# 20190105_ORIGAMI_V1-1-V.net
KiCad netlist of a schematic drawn in EAGLE
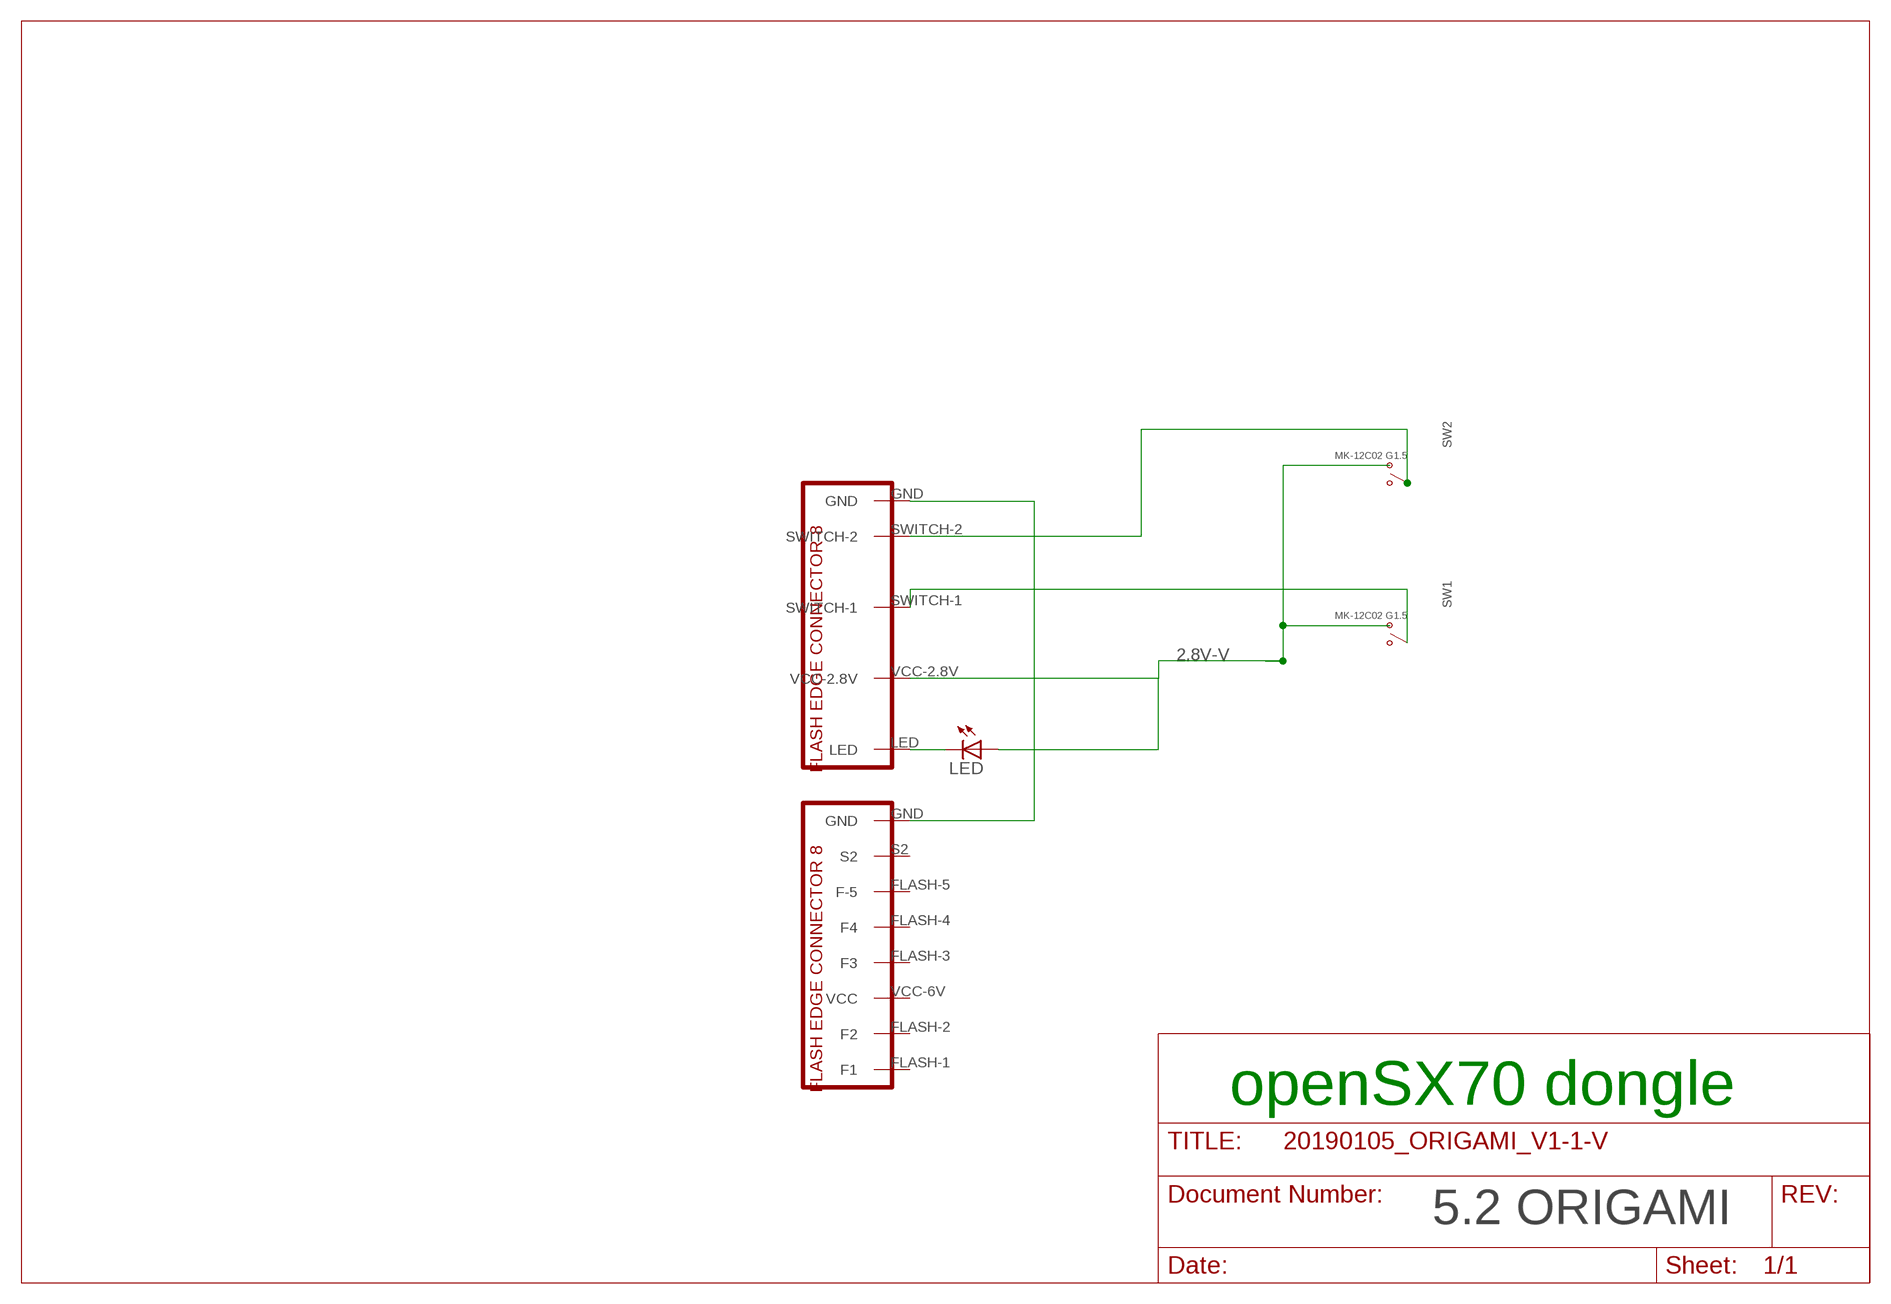
[diagram p0: schematic, sheet 1]

(export (version "E")
  (design (tool "Eeschema 10.0.6"))
  (components
    (comp (ref "LED")
      (value "LEDCHIP-LED0805")
      (footprint "eagle-import:CHIP-LED0805")
      (libsource (lib "eagle-import") (part "LEDCHIP-LED0805"))
    )
    (comp (ref "SW1")
      (value "MK-12C02 G1.5")
      (footprint "eagle-import:SSSS810701")
      (fields (field (name "MF") "ALPS") (field (name "MP") "SSSS810701"))
      (libsource (lib "eagle-import") (part "SSSS810701"))
    )
    (comp (ref "SW2")
      (value "MK-12C02 G1.5")
      (footprint "eagle-import:SSSS810701")
      (fields (field (name "MF") "ALPS") (field (name "MP") "SSSS810701"))
      (libsource (lib "eagle-import") (part "SSSS810701"))
    )
    (comp (ref "U$1")
      (value "FLASH-BRIDGE-SW1-SW2-LED-SMALL")
      (footprint "eagle-import:FLASH-8-BRIDGE-SW1-SW2-LED-SMALL")
      (libsource (lib "eagle-import") (part "FLASH-BRIDGE-SW1-SW2-LED-SMALL"))
    )
    (comp (ref "U$2")
      (value "SX70-FLASH-EDGE8-MALE-LONG")
      (footprint "eagle-import:SX70-FLASH-EDGE8-2")
      (libsource (lib "eagle-import") (part "SX70-FLASH-EDGE8-MALE-LONG"))
    )
  )
  (nets
    (net (code "1") (name "/2.8V-V") (class "Default")
      (node (ref "LED") (pin "A") (pinfunction "A_A") (pintype "passive"))
      (node (ref "SW1") (pin "1") (pinfunction "B_1") (pintype "bidirectional"))
      (node (ref "SW2") (pin "1") (pinfunction "B_1") (pintype "bidirectional"))
      (node (ref "U$1") (pin "VCC-2.8V") (pinfunction "VCC-2.8V_VCC-2.8V") (pintype "bidirectional"))
    )
    (net (code "2") (name "Net-(LED-PadC)") (class "Default")
      (node (ref "LED") (pin "C") (pinfunction "C_C") (pintype "passive"))
      (node (ref "U$1") (pin "LED") (pinfunction "LED_LED") (pintype "bidirectional"))
    )
    (net (code "3") (name "Net-(SW1-COM)") (class "Default")
      (node (ref "SW1") (pin "2") (pinfunction "COM_2") (pintype "bidirectional"))
      (node (ref "U$1") (pin "SWITCH-1") (pinfunction "SWITCH-1_SWITCH-1") (pintype "bidirectional"))
    )
    (net (code "4") (name "Net-(SW2-COM)") (class "Default")
      (node (ref "SW2") (pin "2") (pinfunction "COM_2") (pintype "bidirectional"))
      (node (ref "U$1") (pin "SWITCH-2") (pinfunction "SWITCH-2_SWITCH-2") (pintype "bidirectional"))
    )
    (net (code "5") (name "Net-(U$1-PadGND)") (class "Default")
      (node (ref "U$1") (pin "GND") (pinfunction "GND_GND") (pintype "bidirectional"))
      (node (ref "U$2") (pin "GND") (pinfunction "GND_GND") (pintype "bidirectional"))
    )
    (net (code "6") (name "unconnected-(SW1-A-Pad3)") (class "Default")
      (node (ref "SW1") (pin "3") (pinfunction "A_3") (pintype "bidirectional"))
    )
    (net (code "7") (name "unconnected-(SW2-A-Pad3)") (class "Default")
      (node (ref "SW2") (pin "3") (pinfunction "A_3") (pintype "bidirectional"))
    )
    (net (code "8") (name "unconnected-(U$2-F-5-PadFLASH-5)") (class "Default")
      (node (ref "U$2") (pin "FLASH-5") (pinfunction "F-5_FLASH-5") (pintype "bidirectional"))
    )
    (net (code "9") (name "unconnected-(U$2-F1-PadFLASH-1)") (class "Default")
      (node (ref "U$2") (pin "FLASH-1") (pinfunction "F1_FLASH-1") (pintype "bidirectional"))
    )
    (net (code "10") (name "unconnected-(U$2-F2-PadFLASH-2)") (class "Default")
      (node (ref "U$2") (pin "FLASH-2") (pinfunction "F2_FLASH-2") (pintype "bidirectional"))
    )
    (net (code "11") (name "unconnected-(U$2-F3-PadFLASH-3)") (class "Default")
      (node (ref "U$2") (pin "FLASH-3") (pinfunction "F3_FLASH-3") (pintype "bidirectional"))
    )
    (net (code "12") (name "unconnected-(U$2-F4-PadFLASH-4)") (class "Default")
      (node (ref "U$2") (pin "FLASH-4") (pinfunction "F4_FLASH-4") (pintype "bidirectional"))
    )
    (net (code "13") (name "unconnected-(U$2-PadS2)") (class "Default")
      (node (ref "U$2") (pin "S2") (pinfunction "S2_S2") (pintype "bidirectional"))
    )
    (net (code "14") (name "unconnected-(U$2-VCC-PadVCC-6V)") (class "Default")
      (node (ref "U$2") (pin "VCC-6V") (pinfunction "VCC_VCC-6V") (pintype "bidirectional"))
    )
  )
)
